# SL_Config_2E.net
KiCad netlist of a schematic drawn in Altium Designer
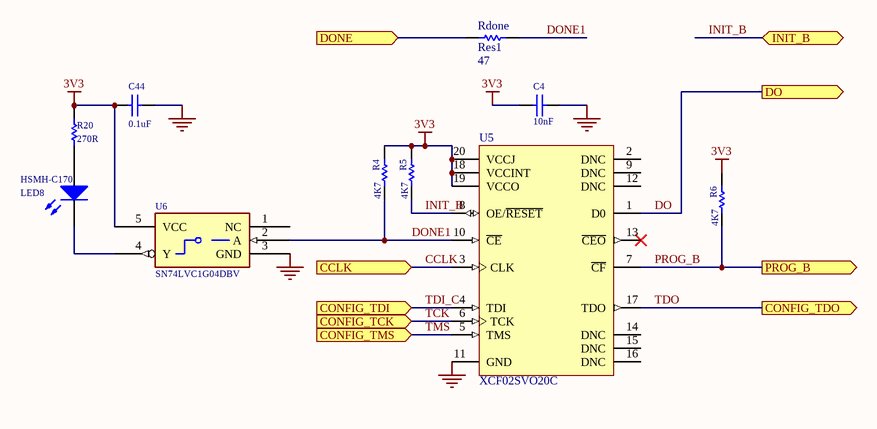
[diagram p0: SL_Config_2E.SchDoc]

(export (version "E")
  (design (tool "Eeschema 10.0.6"))
  (components
    (comp (ref "C4")
      (value "10nF")
      (footprint "CC1608-0603")
      (description "Capacitor")
      (libsource (lib "Test1") (part "CAP"))
    )
    (comp (ref "C44")
      (value "0.1uF")
      (footprint "Altium Nanoboard Project:CC2012-0805")
      (description "Capacitor")
      (libsource (lib "Altium Nanoboard Project") (part "CAP"))
    )
    (comp (ref "LED8")
      (value "HSMH-C170")
      (footprint "Altium Nanoboard Project:SMD _LED")
      (description "Typical RED GaAs SMD LED Agilent make")
      (libsource (lib "Altium Nanoboard Project") (part "HSMX-C670"))
    )
    (comp (ref "R4")
      (value "4K7")
      (footprint "CR2012-0805")
      (description "Resistor")
      (libsource (lib "PassiveSMD") (part "RES"))
    )
    (comp (ref "R5")
      (value "4K7")
      (footprint "CR2012-0805")
      (description "Resistor")
      (libsource (lib "PassiveSMD") (part "RES"))
    )
    (comp (ref "R6")
      (value "4K7")
      (footprint "CR2012-0805")
      (description "Resistor")
      (libsource (lib "PassiveSMD") (part "RES"))
    )
    (comp (ref "R20")
      (value "270R")
      (footprint "CR2012-0805")
      (description "Resistor")
      (libsource (lib "PassiveSMD") (part "RES"))
    )
    (comp (ref "Rdone")
      (value "Res1")
      (footprint "AXIAL-0.3")
      (description "Resistor")
      (fields (field (name "ALTIUM_VALUE") "47") (field (name "PUBLISHER") "Altium Limited"))
      (libsource (lib "Miscellaneous Devices") (part "Res1"))
    )
    (comp (ref "U5")
      (value "XCF02SVO20C")
      (footprint "VO20")
      (libsource (lib "Xilinx XCF") (part "XCF02SVO20C"))
    )
    (comp (ref "U6")
      (value "SN74LVC1G04DBV")
      (footprint "Altium Nanoboard Project:SO-G5/P.95")
      (fields (field (name "MANUFACTURER") "TI"))
      (libsource (lib "Altium Nanoboard Project") (part "SN74AHC1G04DBVR"))
    )
  )
  (nets
    (net (code "1") (name "/CCLK") (class "Default")
      (node (ref "U5") (pin "3") (pinfunction "CLK_3") (pintype "input"))
    )
    (net (code "2") (name "/DO") (class "Default")
      (node (ref "U5") (pin "1") (pinfunction "D0_1") (pintype "tri_state"))
    )
    (net (code "3") (name "/DONE") (class "Default")
      (node (ref "Rdone") (pin "1") (pinfunction "1_1") (pintype "passive"))
    )
    (net (code "4") (name "/DONE1") (class "Default")
      (node (ref "R4") (pin "2") (pinfunction "2_2") (pintype "passive"))
      (node (ref "Rdone") (pin "2") (pinfunction "2_2") (pintype "passive"))
      (node (ref "U5") (pin "10") (pinfunction "~{CE}_10") (pintype "input"))
      (node (ref "U6") (pin "2") (pinfunction "A_2") (pintype "input"))
    )
    (net (code "5") (name "/INIT_B") (class "Default")
      (node (ref "R5") (pin "2") (pinfunction "2_2") (pintype "passive"))
      (node (ref "U5") (pin "8") (pinfunction "OE/~{RESET}_8") (pintype "bidirectional"))
    )
    (net (code "6") (name "/PROG_B") (class "Default")
      (node (ref "R6") (pin "2") (pinfunction "2_2") (pintype "passive"))
      (node (ref "U5") (pin "7") (pinfunction "~{CF}_7") (pintype "open_collector"))
    )
    (net (code "7") (name "/TCK") (class "Default")
      (node (ref "U5") (pin "6") (pinfunction "TCK_6") (pintype "input"))
    )
    (net (code "8") (name "/TDI_C") (class "Default")
      (node (ref "U5") (pin "4") (pinfunction "TDI_4") (pintype "input"))
    )
    (net (code "9") (name "/TDO") (class "Default")
      (node (ref "U5") (pin "17") (pinfunction "TDO_17") (pintype "output"))
    )
    (net (code "10") (name "/TMS") (class "Default")
      (node (ref "U5") (pin "5") (pinfunction "TMS_5") (pintype "input"))
    )
    (net (code "11") (name "3V3") (class "Default")
      (node (ref "C4") (pin "1") (pinfunction "1_1") (pintype "passive"))
      (node (ref "C44") (pin "2") (pinfunction "2_2") (pintype "passive"))
      (node (ref "R20") (pin "2") (pinfunction "2_2") (pintype "passive"))
      (node (ref "R4") (pin "1") (pinfunction "1_1") (pintype "passive"))
      (node (ref "R5") (pin "1") (pinfunction "1_1") (pintype "passive"))
      (node (ref "R6") (pin "1") (pinfunction "1_1") (pintype "passive"))
      (node (ref "U5") (pin "18") (pinfunction "VCCINT_18") (pintype "power_in"))
      (node (ref "U5") (pin "19") (pinfunction "VCCO_19") (pintype "power_in"))
      (node (ref "U5") (pin "20") (pinfunction "VCCJ_20") (pintype "power_in"))
      (node (ref "U6") (pin "5") (pinfunction "VCC_5") (pintype "power_in"))
    )
    (net (code "12") (name "GND") (class "Default")
      (node (ref "C4") (pin "2") (pinfunction "2_2") (pintype "passive"))
      (node (ref "C44") (pin "1") (pinfunction "1_1") (pintype "passive"))
      (node (ref "U5") (pin "11") (pinfunction "GND_11") (pintype "power_in"))
      (node (ref "U6") (pin "3") (pinfunction "GND_3") (pintype "power_in"))
    )
    (net (code "13") (name "Net-(LED8-A)") (class "Default")
      (node (ref "LED8") (pin "1") (pinfunction "A_1") (pintype "passive"))
      (node (ref "R20") (pin "1") (pinfunction "1_1") (pintype "passive"))
    )
    (net (code "14") (name "Net-(LED8-K)") (class "Default")
      (node (ref "LED8") (pin "2") (pinfunction "K_2") (pintype "passive"))
      (node (ref "U6") (pin "4") (pinfunction "Y_4") (pintype "output"))
    )
    (net (code "15") (name "unconnected-(U5-DNC-Pad2)") (class "Default")
      (node (ref "U5") (pin "2") (pinfunction "DNC_2") (pintype "passive"))
    )
    (net (code "16") (name "unconnected-(U5-DNC-Pad9)") (class "Default")
      (node (ref "U5") (pin "9") (pinfunction "DNC_9") (pintype "passive"))
    )
    (net (code "17") (name "unconnected-(U5-DNC-Pad12)") (class "Default")
      (node (ref "U5") (pin "12") (pinfunction "DNC_12") (pintype "passive"))
    )
    (net (code "18") (name "unconnected-(U5-DNC-Pad14)") (class "Default")
      (node (ref "U5") (pin "14") (pinfunction "DNC_14") (pintype "passive"))
    )
    (net (code "19") (name "unconnected-(U5-DNC-Pad15)") (class "Default")
      (node (ref "U5") (pin "15") (pinfunction "DNC_15") (pintype "passive"))
    )
    (net (code "20") (name "unconnected-(U5-DNC-Pad16)") (class "Default")
      (node (ref "U5") (pin "16") (pinfunction "DNC_16") (pintype "passive"))
    )
    (net (code "21") (name "unconnected-(U5-~{CEO}-Pad13)") (class "Default")
      (node (ref "U5") (pin "13") (pinfunction "~{CEO}_13") (pintype "output+no_connect"))
    )
    (net (code "22") (name "unconnected-(U6-NC-Pad1)") (class "Default")
      (node (ref "U6") (pin "1") (pinfunction "NC_1") (pintype "passive"))
    )
  )
)
